# PacBot.net
KiCad netlist of a schematic drawn in Altium Designer
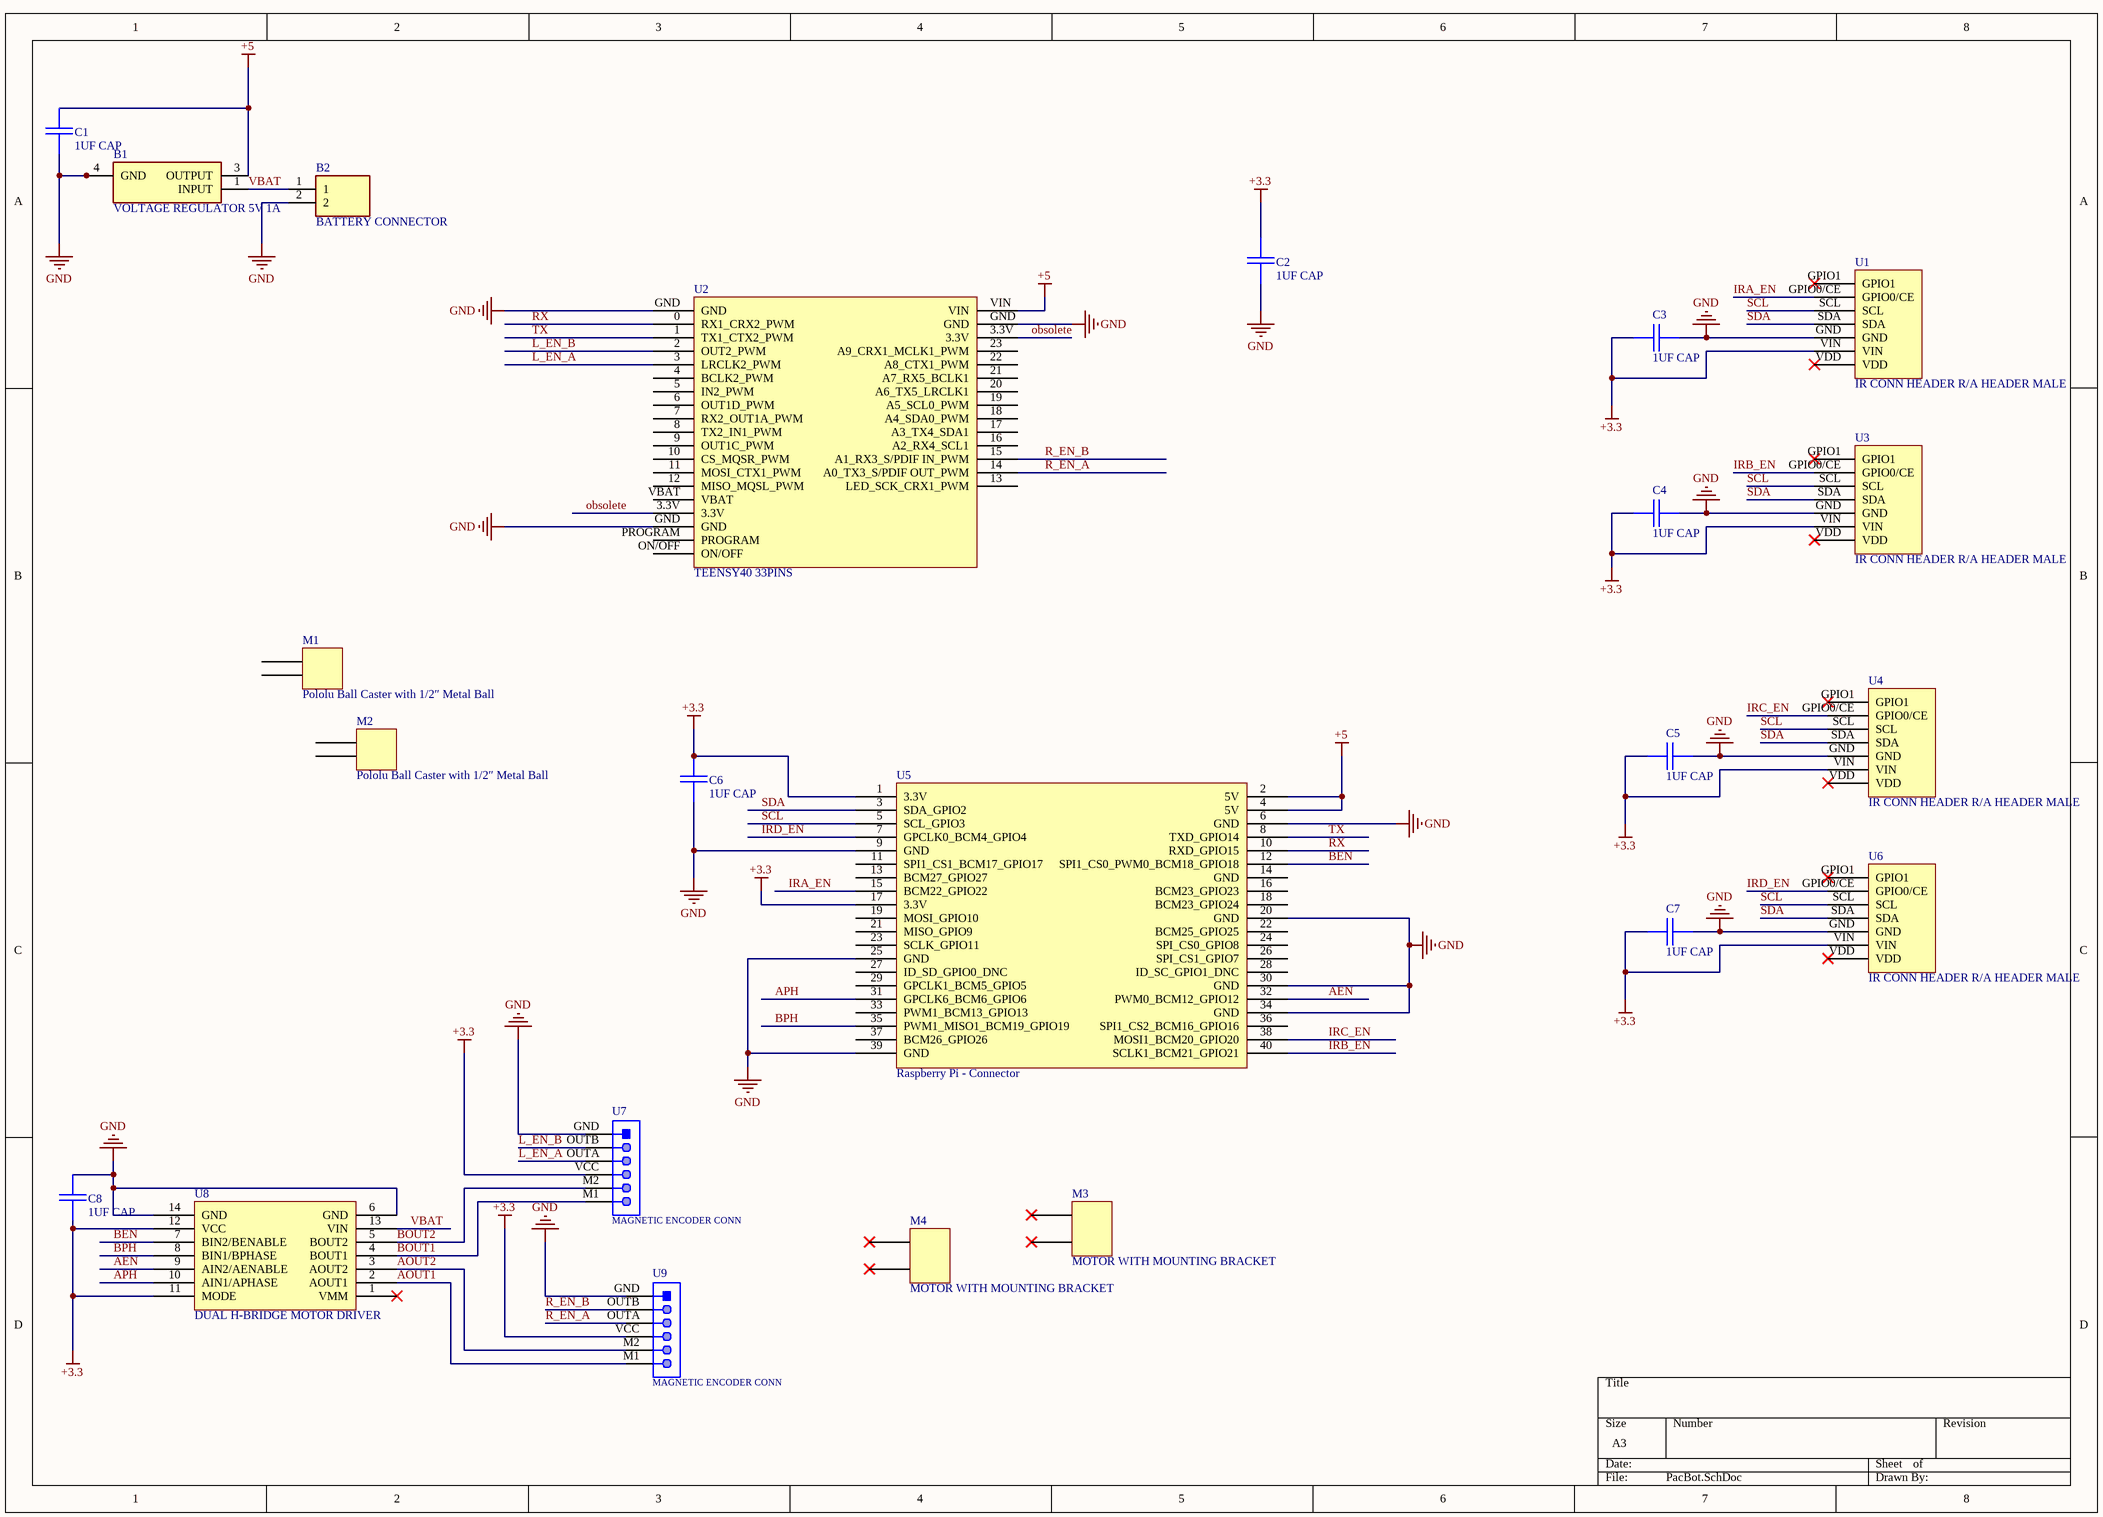
[diagram p0: PacBot.SchDoc]

(export (version "E")
  (design (tool "Eeschema 10.0.6"))
  (components
    (comp (ref "B1")
      (value "VOLTAGE REGULATOR 5V 1A")
      (footprint "D2PAK-STB35NF10T4")
      (fields
        (field (name "MOUSER PART NUMBER") "511-L7805ACD2T-TR")
        (field (name "MANUFACTURER") "STMicroelectronics")
      )
      (libsource (lib "PacBot") (part "L7805ACD2T-TR"))
    )
    (comp (ref "B2")
      (value "BATTERY CONNECTOR")
      (footprint "TE_440054-2")
      (description "HPI Series; 2mm Pitch 2 Way 1 Row Straight PCB Header; Solder Termination; 3A")
      (fields (field (name "MANUFACTURER") "TE Connectivity") (field (name "MP") "440054-2"))
      (libsource (lib "PacBot") (part "440054-2"))
    )
    (comp (ref "C1")
      (value "1UF CAP")
      (footprint "CAPC1608X90N")
      (description "SMD Capacitor X5R(EIA) with Capacitance: 1.0uF Tol. 10%. Rated Voltage: 6.3Vdc")
      (fields
        (field (name "MANUFACTURER") "Murata Electronics")
        (field (name "DIGI-KEY_PART_NUMBER") "490-1550-1-ND")
      )
      (libsource (lib "PacBot") (part "GRM188R60J105KA01D"))
    )
    (comp (ref "C2")
      (value "1UF CAP")
      (footprint "CAPC1608X90N")
      (description "SMD Capacitor X5R(EIA) with Capacitance: 1.0uF Tol. 10%. Rated Voltage: 6.3Vdc")
      (fields
        (field (name "MANUFACTURER") "Murata Electronics")
        (field (name "DIGI-KEY_PART_NUMBER") "490-1550-1-ND")
      )
      (libsource (lib "PacBot") (part "GRM188R60J105KA01D"))
    )
    (comp (ref "C3")
      (value "1UF CAP")
      (footprint "CAPC1608X90N")
      (description "SMD Capacitor X5R(EIA) with Capacitance: 1.0uF Tol. 10%. Rated Voltage: 6.3Vdc")
      (fields
        (field (name "MANUFACTURER") "Murata Electronics")
        (field (name "DIGI-KEY_PART_NUMBER") "490-1550-1-ND")
      )
      (libsource (lib "PacBot") (part "GRM188R60J105KA01D"))
    )
    (comp (ref "C4")
      (value "1UF CAP")
      (footprint "CAPC1608X90N")
      (description "SMD Capacitor X5R(EIA) with Capacitance: 1.0uF Tol. 10%. Rated Voltage: 6.3Vdc")
      (fields
        (field (name "MANUFACTURER") "Murata Electronics")
        (field (name "DIGI-KEY_PART_NUMBER") "490-1550-1-ND")
      )
      (libsource (lib "PacBot") (part "GRM188R60J105KA01D"))
    )
    (comp (ref "C5")
      (value "1UF CAP")
      (footprint "CAPC1608X90N")
      (description "SMD Capacitor X5R(EIA) with Capacitance: 1.0uF Tol. 10%. Rated Voltage: 6.3Vdc")
      (fields
        (field (name "MANUFACTURER") "Murata Electronics")
        (field (name "DIGI-KEY_PART_NUMBER") "490-1550-1-ND")
      )
      (libsource (lib "PacBot") (part "GRM188R60J105KA01D"))
    )
    (comp (ref "C6")
      (value "1UF CAP")
      (footprint "CAPC1608X90N")
      (description "SMD Capacitor X5R(EIA) with Capacitance: 1.0uF Tol. 10%. Rated Voltage: 6.3Vdc")
      (fields
        (field (name "MANUFACTURER") "Murata Electronics")
        (field (name "DIGI-KEY_PART_NUMBER") "490-1550-1-ND")
      )
      (libsource (lib "PacBot") (part "GRM188R60J105KA01D"))
    )
    (comp (ref "C7")
      (value "1UF CAP")
      (footprint "CAPC1608X90N")
      (description "SMD Capacitor X5R(EIA) with Capacitance: 1.0uF Tol. 10%. Rated Voltage: 6.3Vdc")
      (fields
        (field (name "MANUFACTURER") "Murata Electronics")
        (field (name "DIGI-KEY_PART_NUMBER") "490-1550-1-ND")
      )
      (libsource (lib "PacBot") (part "GRM188R60J105KA01D"))
    )
    (comp (ref "C8")
      (value "1UF CAP")
      (footprint "CAPC1608X90N")
      (description "SMD Capacitor X5R(EIA) with Capacitance: 1.0uF Tol. 10%. Rated Voltage: 6.3Vdc")
      (fields
        (field (name "MANUFACTURER") "Murata Electronics")
        (field (name "DIGI-KEY_PART_NUMBER") "490-1550-1-ND")
      )
      (libsource (lib "PacBot") (part "GRM188R60J105KA01D"))
    )
    (comp (ref "M1")
      (value "Pololu Ball Caster with 1/2″ Metal Ball")
      (footprint "Ball_Caster")
      (fields (field (name "MANUFACTURER") "Pololu"))
      (libsource (lib "PacBot") (part "Ball_Caster"))
    )
    (comp (ref "M2")
      (value "Pololu Ball Caster with 1/2″ Metal Ball")
      (footprint "Ball_Caster")
      (fields (field (name "MANUFACTURER") "Pololu"))
      (libsource (lib "PacBot") (part "Ball_Caster"))
    )
    (comp (ref "M3")
      (value "MOTOR WITH MOUNTING BRACKET")
      (footprint "MOTOR")
      (fields (field (name "MANUFACTURER") "Pololu"))
      (libsource (lib "PacBot") (part "MOTOR"))
    )
    (comp (ref "M4")
      (value "MOTOR WITH MOUNTING BRACKET")
      (footprint "MOTOR")
      (fields (field (name "MANUFACTURER") "Pololu"))
      (libsource (lib "PacBot") (part "MOTOR"))
    )
    (comp (ref "U1")
      (value "IR CONN HEADER R/A HEADER MALE")
      (footprint "VL6180X")
      (fields (field (name "MANUFACTURER") "Digi-Key"))
      (libsource (lib "PacBot") (part "VL6180X"))
    )
    (comp (ref "U2")
      (value "TEENSY40 33PINS")
      (footprint "TEENSY40")
      (description "Teensy USB Board, Version 4.0. 32 bits arduino compatible microcontroller")
      (fields (field (name "MANUFACTURER") "PJRC Store"))
      (libsource (lib "PacBot") (part "TEENSY40"))
    )
    (comp (ref "U3")
      (value "IR CONN HEADER R/A HEADER MALE")
      (footprint "VL6180X")
      (fields (field (name "MANUFACTURER") "Digi-Key"))
      (libsource (lib "PacBot") (part "VL6180X"))
    )
    (comp (ref "U4")
      (value "IR CONN HEADER R/A HEADER MALE")
      (footprint "VL6180X")
      (fields (field (name "MANUFACTURER") "Digi-Key"))
      (libsource (lib "PacBot") (part "VL6180X"))
    )
    (comp (ref "U5")
      (value "Raspberry Pi - Connector")
      (footprint "RPY")
      (description "RASPBERRYPI GPIO MALE HEADER")
      (fields (field (name "MANUFACTURER") "Mouser"))
      (libsource (lib "PacBot") (part "RPY"))
    )
    (comp (ref "U6")
      (value "IR CONN HEADER R/A HEADER MALE")
      (footprint "VL6180X")
      (fields (field (name "MANUFACTURER") "Digi-Key"))
      (libsource (lib "PacBot") (part "VL6180X"))
    )
    (comp (ref "U7")
      (value "MAGNETIC ENCODER CONN")
      (footprint "61300611121")
      (description "THT Vertical Pin Header WR-PHD, Pitch 2.54 mm, Single Row, 6 pins")
      (fields (field (name "MANUFACTURER") "Wurth Elektronik") (field (name "PUBLISHER") "WurthElektronik"))
      (libsource (lib "PacBot") (part "CMP-1502-01070-1"))
    )
    (comp (ref "U8")
      (value "DUAL H-BRIDGE MOTOR DRIVER")
      (footprint "DRV8835")
      (fields (field (name "MANUFACTURER") "Pololu"))
      (libsource (lib "PacBot") (part "DRV8835"))
    )
    (comp (ref "U9")
      (value "MAGNETIC ENCODER CONN")
      (footprint "61300611121")
      (description "THT Vertical Pin Header WR-PHD, Pitch 2.54 mm, Single Row, 6 pins")
      (fields (field (name "MANUFACTURER") "Wurth Elektronik") (field (name "PUBLISHER") "WurthElektronik"))
      (libsource (lib "PacBot") (part "CMP-1502-01070-1"))
    )
  )
  (nets
    (net (code "1") (name "+3.3") (class "Default")
      (node (ref "C2") (pin "1") (pinfunction "1_1") (pintype "passive"))
      (node (ref "C3") (pin "1") (pinfunction "1_1") (pintype "passive"))
      (node (ref "C4") (pin "1") (pinfunction "1_1") (pintype "passive"))
      (node (ref "C5") (pin "1") (pinfunction "1_1") (pintype "passive"))
      (node (ref "C6") (pin "2") (pinfunction "2_2") (pintype "passive"))
      (node (ref "C7") (pin "1") (pinfunction "1_1") (pintype "passive"))
      (node (ref "C8") (pin "1") (pinfunction "1_1") (pintype "passive"))
      (node (ref "U1") (pin "VIN") (pinfunction "VIN_VIN") (pintype "passive"))
      (node (ref "U3") (pin "VIN") (pinfunction "VIN_VIN") (pintype "passive"))
      (node (ref "U4") (pin "VIN") (pinfunction "VIN_VIN") (pintype "passive"))
      (node (ref "U5") (pin "1") (pinfunction "3.3V_1") (pintype "passive"))
      (node (ref "U5") (pin "17") (pinfunction "3.3V_17") (pintype "passive"))
      (node (ref "U6") (pin "VIN") (pinfunction "VIN_VIN") (pintype "passive"))
      (node (ref "U7") (pin "VCC") (pinfunction "VCC_VCC") (pintype "passive"))
      (node (ref "U8") (pin "11") (pinfunction "MODE_11") (pintype "passive"))
      (node (ref "U8") (pin "12") (pinfunction "VCC_12") (pintype "passive"))
      (node (ref "U9") (pin "VCC") (pinfunction "VCC_VCC") (pintype "passive"))
    )
    (net (code "2") (name "+5") (class "Default")
      (node (ref "B1") (pin "3") (pinfunction "OUTPUT_3") (pintype "passive"))
      (node (ref "C1") (pin "1") (pinfunction "1_1") (pintype "passive"))
      (node (ref "U2") (pin "VIN") (pinfunction "VIN_VIN") (pintype "passive"))
      (node (ref "U5") (pin "2") (pinfunction "5V_2") (pintype "passive"))
      (node (ref "U5") (pin "4") (pinfunction "5V_4") (pintype "passive"))
    )
    (net (code "3") (name "/AEN") (class "Default")
      (node (ref "U5") (pin "32") (pinfunction "PWM0_BCM12_GPIO12_32") (pintype "passive"))
      (node (ref "U8") (pin "9") (pinfunction "AIN2/AENABLE_9") (pintype "passive"))
    )
    (net (code "4") (name "/AOUT1") (class "Default")
      (node (ref "U8") (pin "2") (pinfunction "AOUT1_2") (pintype "passive"))
      (node (ref "U9") (pin "M1") (pinfunction "M1_M1") (pintype "passive"))
    )
    (net (code "5") (name "/AOUT2") (class "Default")
      (node (ref "U8") (pin "3") (pinfunction "AOUT2_3") (pintype "passive"))
      (node (ref "U9") (pin "M2") (pinfunction "M2_M2") (pintype "passive"))
    )
    (net (code "6") (name "/APH") (class "Default")
      (node (ref "U5") (pin "31") (pinfunction "GPCLK6_BCM6_GPIO6_31") (pintype "passive"))
      (node (ref "U8") (pin "10") (pinfunction "AIN1/APHASE_10") (pintype "passive"))
    )
    (net (code "7") (name "/BEN") (class "Default")
      (node (ref "U5") (pin "12") (pinfunction "SPI1_CS0_PWM0_BCM18_GPIO18_12") (pintype "passive"))
      (node (ref "U8") (pin "7") (pinfunction "BIN2/BENABLE_7") (pintype "passive"))
    )
    (net (code "8") (name "/BOUT1") (class "Default")
      (node (ref "U7") (pin "M1") (pinfunction "M1_M1") (pintype "passive"))
      (node (ref "U8") (pin "4") (pinfunction "BOUT1_4") (pintype "passive"))
    )
    (net (code "9") (name "/BOUT2") (class "Default")
      (node (ref "U7") (pin "M2") (pinfunction "M2_M2") (pintype "passive"))
      (node (ref "U8") (pin "5") (pinfunction "BOUT2_5") (pintype "passive"))
    )
    (net (code "10") (name "/BPH") (class "Default")
      (node (ref "U5") (pin "35") (pinfunction "PWM1_MISO1_BCM19_GPIO19_35") (pintype "passive"))
      (node (ref "U8") (pin "8") (pinfunction "BIN1/BPHASE_8") (pintype "passive"))
    )
    (net (code "11") (name "/IRA_EN") (class "Default")
      (node (ref "U1") (pin "GPIO0/CE") (pinfunction "GPIO0/CE_GPIO0/CE") (pintype "passive"))
      (node (ref "U5") (pin "15") (pinfunction "BCM22_GPIO22_15") (pintype "passive"))
    )
    (net (code "12") (name "/IRB_EN") (class "Default")
      (node (ref "U3") (pin "GPIO0/CE") (pinfunction "GPIO0/CE_GPIO0/CE") (pintype "passive"))
      (node (ref "U5") (pin "40") (pinfunction "SCLK1_BCM21_GPIO21_40") (pintype "passive"))
    )
    (net (code "13") (name "/IRC_EN") (class "Default")
      (node (ref "U4") (pin "GPIO0/CE") (pinfunction "GPIO0/CE_GPIO0/CE") (pintype "passive"))
      (node (ref "U5") (pin "38") (pinfunction "MOSI1_BCM20_GPIO20_38") (pintype "passive"))
    )
    (net (code "14") (name "/IRD_EN") (class "Default")
      (node (ref "U5") (pin "7") (pinfunction "GPCLK0_BCM4_GPIO4_7") (pintype "passive"))
      (node (ref "U6") (pin "GPIO0/CE") (pinfunction "GPIO0/CE_GPIO0/CE") (pintype "passive"))
    )
    (net (code "15") (name "/L_EN_A") (class "Default")
      (node (ref "U2") (pin "3") (pinfunction "LRCLK2_PWM_3") (pintype "passive"))
      (node (ref "U7") (pin "OUTA") (pinfunction "OUTA_OUTA") (pintype "passive"))
    )
    (net (code "16") (name "/L_EN_B") (class "Default")
      (node (ref "U2") (pin "2") (pinfunction "OUT2_PWM_2") (pintype "passive"))
      (node (ref "U7") (pin "OUTB") (pinfunction "OUTB_OUTB") (pintype "passive"))
    )
    (net (code "17") (name "/RX") (class "Default")
      (node (ref "U2") (pin "0") (pinfunction "RX1_CRX2_PWM_0") (pintype "passive"))
      (node (ref "U5") (pin "10") (pinfunction "RXD_GPIO15_10") (pintype "passive"))
    )
    (net (code "18") (name "/R_EN_A") (class "Default")
      (node (ref "U2") (pin "14") (pinfunction "A0_TX3_S/PDIF_OUT_PWM_14") (pintype "passive"))
      (node (ref "U9") (pin "OUTA") (pinfunction "OUTA_OUTA") (pintype "passive"))
    )
    (net (code "19") (name "/R_EN_B") (class "Default")
      (node (ref "U2") (pin "15") (pinfunction "A1_RX3_S/PDIF_IN_PWM_15") (pintype "passive"))
      (node (ref "U9") (pin "OUTB") (pinfunction "OUTB_OUTB") (pintype "passive"))
    )
    (net (code "20") (name "/SCL") (class "Default")
      (node (ref "U1") (pin "SCL") (pinfunction "SCL_SCL") (pintype "passive"))
      (node (ref "U3") (pin "SCL") (pinfunction "SCL_SCL") (pintype "passive"))
      (node (ref "U4") (pin "SCL") (pinfunction "SCL_SCL") (pintype "passive"))
      (node (ref "U5") (pin "5") (pinfunction "SCL_GPIO3_5") (pintype "passive"))
      (node (ref "U6") (pin "SCL") (pinfunction "SCL_SCL") (pintype "passive"))
    )
    (net (code "21") (name "/SDA") (class "Default")
      (node (ref "U1") (pin "SDA") (pinfunction "SDA_SDA") (pintype "passive"))
      (node (ref "U3") (pin "SDA") (pinfunction "SDA_SDA") (pintype "passive"))
      (node (ref "U4") (pin "SDA") (pinfunction "SDA_SDA") (pintype "passive"))
      (node (ref "U5") (pin "3") (pinfunction "SDA_GPIO2_3") (pintype "passive"))
      (node (ref "U6") (pin "SDA") (pinfunction "SDA_SDA") (pintype "passive"))
    )
    (net (code "22") (name "/TX") (class "Default")
      (node (ref "U2") (pin "1") (pinfunction "TX1_CTX2_PWM_1") (pintype "passive"))
      (node (ref "U5") (pin "8") (pinfunction "TXD_GPIO14_8") (pintype "passive"))
    )
    (net (code "23") (name "/VBAT") (class "Default")
      (node (ref "B1") (pin "1") (pinfunction "INPUT_1") (pintype "passive"))
      (node (ref "B2") (pin "1") (pinfunction "1_1") (pintype "passive"))
      (node (ref "U8") (pin "13") (pinfunction "VIN_13") (pintype "passive"))
    )
    (net (code "24") (name "/obsolete") (class "Default")
      (node (ref "U2") (pin "3.3V") (pinfunction "3.3V_3.3V") (pintype "passive"))
    )
    (net (code "25") (name "GND") (class "Default")
      (node (ref "B1") (pin "4") (pinfunction "GND_4") (pintype "passive"))
      (node (ref "B2") (pin "2") (pinfunction "2_2") (pintype "passive"))
      (node (ref "C1") (pin "2") (pinfunction "2_2") (pintype "passive"))
      (node (ref "C2") (pin "2") (pinfunction "2_2") (pintype "passive"))
      (node (ref "C3") (pin "2") (pinfunction "2_2") (pintype "passive"))
      (node (ref "C4") (pin "2") (pinfunction "2_2") (pintype "passive"))
      (node (ref "C5") (pin "2") (pinfunction "2_2") (pintype "passive"))
      (node (ref "C6") (pin "1") (pinfunction "1_1") (pintype "passive"))
      (node (ref "C7") (pin "2") (pinfunction "2_2") (pintype "passive"))
      (node (ref "C8") (pin "2") (pinfunction "2_2") (pintype "passive"))
      (node (ref "U1") (pin "GND") (pinfunction "GND_GND") (pintype "passive"))
      (node (ref "U2") (pin "GND") (pinfunction "GND_GND") (pintype "passive"))
      (node (ref "U3") (pin "GND") (pinfunction "GND_GND") (pintype "passive"))
      (node (ref "U4") (pin "GND") (pinfunction "GND_GND") (pintype "passive"))
      (node (ref "U5") (pin "20") (pinfunction "GND_20") (pintype "passive"))
      (node (ref "U5") (pin "25") (pinfunction "GND_25") (pintype "passive"))
      (node (ref "U5") (pin "30") (pinfunction "GND_30") (pintype "passive"))
      (node (ref "U5") (pin "34") (pinfunction "GND_34") (pintype "passive"))
      (node (ref "U5") (pin "39") (pinfunction "GND_39") (pintype "passive"))
      (node (ref "U5") (pin "6") (pinfunction "GND_6") (pintype "passive"))
      (node (ref "U5") (pin "9") (pinfunction "GND_9") (pintype "passive"))
      (node (ref "U6") (pin "GND") (pinfunction "GND_GND") (pintype "passive"))
      (node (ref "U7") (pin "GND") (pinfunction "GND_GND") (pintype "passive"))
      (node (ref "U8") (pin "14") (pinfunction "GND_14") (pintype "passive"))
      (node (ref "U8") (pin "6") (pinfunction "GND_6") (pintype "passive"))
      (node (ref "U9") (pin "GND") (pinfunction "GND_GND") (pintype "passive"))
    )
    (net (code "26") (name "unconnected-(M1-Pad1)") (class "Default")
      (node (ref "M1") (pin "1") (pinfunction "1_1") (pintype "passive"))
    )
    (net (code "27") (name "unconnected-(M1-Pad2)") (class "Default")
      (node (ref "M1") (pin "2") (pinfunction "2_2") (pintype "passive"))
    )
    (net (code "28") (name "unconnected-(M2-Pad1)") (class "Default")
      (node (ref "M2") (pin "1") (pinfunction "1_1") (pintype "passive"))
    )
    (net (code "29") (name "unconnected-(M2-Pad2)") (class "Default")
      (node (ref "M2") (pin "2") (pinfunction "2_2") (pintype "passive"))
    )
    (net (code "30") (name "unconnected-(M3-Pad1)") (class "Default")
      (node (ref "M3") (pin "1") (pinfunction "1_1") (pintype "passive+no_connect"))
    )
    (net (code "31") (name "unconnected-(M3-PadVDD)") (class "Default")
      (node (ref "M3") (pin "VDD") (pinfunction "VDD_VDD") (pintype "passive+no_connect"))
    )
    (net (code "32") (name "unconnected-(M4-Pad1)") (class "Default")
      (node (ref "M4") (pin "1") (pinfunction "1_1") (pintype "passive+no_connect"))
    )
    (net (code "33") (name "unconnected-(M4-PadVDD)") (class "Default")
      (node (ref "M4") (pin "VDD") (pinfunction "VDD_VDD") (pintype "passive+no_connect"))
    )
    (net (code "34") (name "unconnected-(U1-PadGPIO1)") (class "Default")
      (node (ref "U1") (pin "GPIO1") (pinfunction "GPIO1_GPIO1") (pintype "passive+no_connect"))
    )
    (net (code "35") (name "unconnected-(U1-PadVDD)") (class "Default")
      (node (ref "U1") (pin "VDD") (pinfunction "VDD_VDD") (pintype "passive+no_connect"))
    )
    (net (code "36") (name "unconnected-(U2-A2_RX4_SCL1-Pad16)") (class "Default")
      (node (ref "U2") (pin "16") (pinfunction "A2_RX4_SCL1_16") (pintype "passive"))
    )
    (net (code "37") (name "unconnected-(U2-A3_TX4_SDA1-Pad17)") (class "Default")
      (node (ref "U2") (pin "17") (pinfunction "A3_TX4_SDA1_17") (pintype "passive"))
    )
    (net (code "38") (name "unconnected-(U2-A4_SDA0_PWM-Pad18)") (class "Default")
      (node (ref "U2") (pin "18") (pinfunction "A4_SDA0_PWM_18") (pintype "passive"))
    )
    (net (code "39") (name "unconnected-(U2-A5_SCL0_PWM-Pad19)") (class "Default")
      (node (ref "U2") (pin "19") (pinfunction "A5_SCL0_PWM_19") (pintype "passive"))
    )
    (net (code "40") (name "unconnected-(U2-A6_TX5_LRCLK1-Pad20)") (class "Default")
      (node (ref "U2") (pin "20") (pinfunction "A6_TX5_LRCLK1_20") (pintype "passive"))
    )
    (net (code "41") (name "unconnected-(U2-A7_RX5_BCLK1-Pad21)") (class "Default")
      (node (ref "U2") (pin "21") (pinfunction "A7_RX5_BCLK1_21") (pintype "passive"))
    )
    (net (code "42") (name "unconnected-(U2-A8_CTX1_PWM-Pad22)") (class "Default")
      (node (ref "U2") (pin "22") (pinfunction "A8_CTX1_PWM_22") (pintype "passive"))
    )
    (net (code "43") (name "unconnected-(U2-A9_CRX1_MCLK1_PWM-Pad23)") (class "Default")
      (node (ref "U2") (pin "23") (pinfunction "A9_CRX1_MCLK1_PWM_23") (pintype "passive"))
    )
    (net (code "44") (name "unconnected-(U2-BCLK2_PWM-Pad4)") (class "Default")
      (node (ref "U2") (pin "4") (pinfunction "BCLK2_PWM_4") (pintype "passive"))
    )
    (net (code "45") (name "unconnected-(U2-CS_MQSR_PWM-Pad10)") (class "Default")
      (node (ref "U2") (pin "10") (pinfunction "CS_MQSR_PWM_10") (pintype "passive"))
    )
    (net (code "46") (name "unconnected-(U2-IN2_PWM-Pad5)") (class "Default")
      (node (ref "U2") (pin "5") (pinfunction "IN2_PWM_5") (pintype "passive"))
    )
    (net (code "47") (name "unconnected-(U2-LED_SCK_CRX1_PWM-Pad13)") (class "Default")
      (node (ref "U2") (pin "13") (pinfunction "LED_SCK_CRX1_PWM_13") (pintype "passive"))
    )
    (net (code "48") (name "unconnected-(U2-MISO_MQSL_PWM-Pad12)") (class "Default")
      (node (ref "U2") (pin "12") (pinfunction "MISO_MQSL_PWM_12") (pintype "passive"))
    )
    (net (code "49") (name "unconnected-(U2-MOSI_CTX1_PWM-Pad11)") (class "Default")
      (node (ref "U2") (pin "11") (pinfunction "MOSI_CTX1_PWM_11") (pintype "passive"))
    )
    (net (code "50") (name "unconnected-(U2-OUT1C_PWM-Pad9)") (class "Default")
      (node (ref "U2") (pin "9") (pinfunction "OUT1C_PWM_9") (pintype "passive"))
    )
    (net (code "51") (name "unconnected-(U2-OUT1D_PWM-Pad6)") (class "Default")
      (node (ref "U2") (pin "6") (pinfunction "OUT1D_PWM_6") (pintype "passive"))
    )
    (net (code "52") (name "unconnected-(U2-PadON{slash}OFF)") (class "Default")
      (node (ref "U2") (pin "ON/OFF") (pinfunction "ON/OFF_ON/OFF") (pintype "passive"))
    )
    (net (code "53") (name "unconnected-(U2-PadPROGRAM)") (class "Default")
      (node (ref "U2") (pin "PROGRAM") (pinfunction "PROGRAM_PROGRAM") (pintype "passive"))
    )
    (net (code "54") (name "unconnected-(U2-PadVBAT)") (class "Default")
      (node (ref "U2") (pin "VBAT") (pinfunction "VBAT_VBAT") (pintype "passive"))
    )
    (net (code "55") (name "unconnected-(U2-RX2_OUT1A_PWM-Pad7)") (class "Default")
      (node (ref "U2") (pin "7") (pinfunction "RX2_OUT1A_PWM_7") (pintype "passive"))
    )
    (net (code "56") (name "unconnected-(U2-TX2_IN1_PWM-Pad8)") (class "Default")
      (node (ref "U2") (pin "8") (pinfunction "TX2_IN1_PWM_8") (pintype "passive"))
    )
    (net (code "57") (name "unconnected-(U3-PadGPIO1)") (class "Default")
      (node (ref "U3") (pin "GPIO1") (pinfunction "GPIO1_GPIO1") (pintype "passive+no_connect"))
    )
    (net (code "58") (name "unconnected-(U3-PadVDD)") (class "Default")
      (node (ref "U3") (pin "VDD") (pinfunction "VDD_VDD") (pintype "passive+no_connect"))
    )
    (net (code "59") (name "unconnected-(U4-PadGPIO1)") (class "Default")
      (node (ref "U4") (pin "GPIO1") (pinfunction "GPIO1_GPIO1") (pintype "passive+no_connect"))
    )
    (net (code "60") (name "unconnected-(U4-PadVDD)") (class "Default")
      (node (ref "U4") (pin "VDD") (pinfunction "VDD_VDD") (pintype "passive+no_connect"))
    )
    (net (code "61") (name "unconnected-(U5-BCM23_GPIO23-Pad16)") (class "Default")
      (node (ref "U5") (pin "16") (pinfunction "BCM23_GPIO23_16") (pintype "passive"))
    )
    (net (code "62") (name "unconnected-(U5-BCM23_GPIO24-Pad18)") (class "Default")
      (node (ref "U5") (pin "18") (pinfunction "BCM23_GPIO24_18") (pintype "passive"))
    )
    (net (code "63") (name "unconnected-(U5-BCM25_GPIO25-Pad22)") (class "Default")
      (node (ref "U5") (pin "22") (pinfunction "BCM25_GPIO25_22") (pintype "passive"))
    )
    (net (code "64") (name "unconnected-(U5-BCM26_GPIO26-Pad37)") (class "Default")
      (node (ref "U5") (pin "37") (pinfunction "BCM26_GPIO26_37") (pintype "passive"))
    )
    (net (code "65") (name "unconnected-(U5-BCM27_GPIO27-Pad13)") (class "Default")
      (node (ref "U5") (pin "13") (pinfunction "BCM27_GPIO27_13") (pintype "passive"))
    )
    (net (code "66") (name "unconnected-(U5-GND-Pad14)") (class "Default")
      (node (ref "U5") (pin "14") (pinfunction "GND_14") (pintype "passive"))
    )
    (net (code "67") (name "unconnected-(U5-GPCLK1_BCM5_GPIO5-Pad29)") (class "Default")
      (node (ref "U5") (pin "29") (pinfunction "GPCLK1_BCM5_GPIO5_29") (pintype "passive"))
    )
    (net (code "68") (name "unconnected-(U5-ID_SC_GPIO1_DNC-Pad28)") (class "Default")
      (node (ref "U5") (pin "28") (pinfunction "ID_SC_GPIO1_DNC_28") (pintype "passive"))
    )
    (net (code "69") (name "unconnected-(U5-ID_SD_GPIO0_DNC-Pad27)") (class "Default")
      (node (ref "U5") (pin "27") (pinfunction "ID_SD_GPIO0_DNC_27") (pintype "passive"))
    )
    (net (code "70") (name "unconnected-(U5-MISO_GPIO9-Pad21)") (class "Default")
      (node (ref "U5") (pin "21") (pinfunction "MISO_GPIO9_21") (pintype "passive"))
    )
    (net (code "71") (name "unconnected-(U5-MOSI_GPIO10-Pad19)") (class "Default")
      (node (ref "U5") (pin "19") (pinfunction "MOSI_GPIO10_19") (pintype "passive"))
    )
    (net (code "72") (name "unconnected-(U5-PWM1_BCM13_GPIO13-Pad33)") (class "Default")
      (node (ref "U5") (pin "33") (pinfunction "PWM1_BCM13_GPIO13_33") (pintype "passive"))
    )
    (net (code "73") (name "unconnected-(U5-SCLK_GPIO11-Pad23)") (class "Default")
      (node (ref "U5") (pin "23") (pinfunction "SCLK_GPIO11_23") (pintype "passive"))
    )
    (net (code "74") (name "unconnected-(U5-SPI1_CS1_BCM17_GPIO17-Pad11)") (class "Default")
      (node (ref "U5") (pin "11") (pinfunction "SPI1_CS1_BCM17_GPIO17_11") (pintype "passive"))
    )
    (net (code "75") (name "unconnected-(U5-SPI1_CS2_BCM16_GPIO16-Pad36)") (class "Default")
      (node (ref "U5") (pin "36") (pinfunction "SPI1_CS2_BCM16_GPIO16_36") (pintype "passive"))
    )
    (net (code "76") (name "unconnected-(U5-SPI_CS0_GPIO8-Pad24)") (class "Default")
      (node (ref "U5") (pin "24") (pinfunction "SPI_CS0_GPIO8_24") (pintype "passive"))
    )
    (net (code "77") (name "unconnected-(U5-SPI_CS1_GPIO7-Pad26)") (class "Default")
      (node (ref "U5") (pin "26") (pinfunction "SPI_CS1_GPIO7_26") (pintype "passive"))
    )
    (net (code "78") (name "unconnected-(U6-PadGPIO1)") (class "Default")
      (node (ref "U6") (pin "GPIO1") (pinfunction "GPIO1_GPIO1") (pintype "passive+no_connect"))
    )
    (net (code "79") (name "unconnected-(U6-PadVDD)") (class "Default")
      (node (ref "U6") (pin "VDD") (pinfunction "VDD_VDD") (pintype "passive+no_connect"))
    )
    (net (code "80") (name "unconnected-(U8-VMM-Pad1)") (class "Default")
      (node (ref "U8") (pin "1") (pinfunction "VMM_1") (pintype "passive+no_connect"))
    )
  )
)
